# ICSL_PS_Combined_Shared.net
KiCad netlist of a schematic drawn in Altium Designer
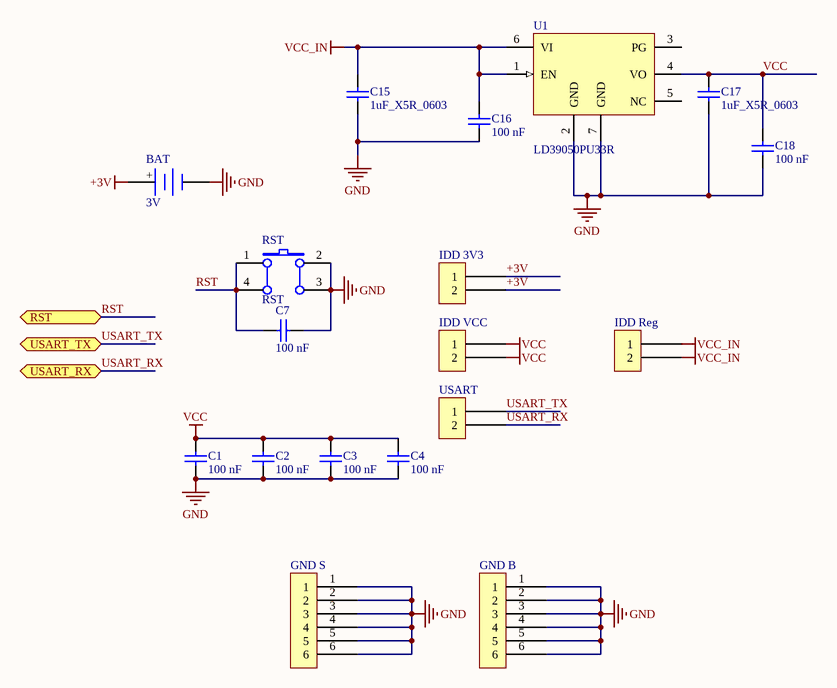
[diagram p0: ICSL_PS_Combined_Shared.SchDoc]

(export (version "E")
  (design (tool "Eeschema 10.0.6"))
  (components
    (comp (ref "BAT")
      (value "3V")
      (footprint "PCB-ltikzgtn8bqt3ncdf2ka-1")
      (description "HOLDER BATTERY DUAL CELL 20MM")
      (fields
        (field (name "MANUFACTURER") "Keystone Electronics")
        (field (name "MANUFACTURER PART NUMBER") "1026")
      )
      (libsource (lib "Octopart library") (part "SYM-19352663-1"))
    )
    (comp (ref "C1")
      (value "100 nF")
      (footprint "CAPC1608X87X35LL15T15")
      (description "Multilayer Ceramic Capacitors MLCC - SMD/SMT 50volts 82000pF X7R 10%")
      (libsource (lib "Octopart library") (part "CAP-2"))
    )
    (comp (ref "C2")
      (value "100 nF")
      (footprint "CAPC1608X87X35LL15T15")
      (description "Multilayer Ceramic Capacitors MLCC - SMD/SMT 50volts 82000pF X7R 10%")
      (libsource (lib "Octopart library") (part "CAP-2"))
    )
    (comp (ref "C3")
      (value "100 nF")
      (footprint "CAPC1608X87X35LL15T15")
      (description "Multilayer Ceramic Capacitors MLCC - SMD/SMT 50volts 82000pF X7R 10%")
      (libsource (lib "Octopart library") (part "CAP-2"))
    )
    (comp (ref "C4")
      (value "100 nF")
      (footprint "CAPC1608X87X35LL15T15")
      (description "Multilayer Ceramic Capacitors MLCC - SMD/SMT 50volts 82000pF X7R 10%")
      (libsource (lib "Octopart library") (part "CAP-2"))
    )
    (comp (ref "C7")
      (value "100 nF")
      (footprint "CAPC1608X87X35LL15T15")
      (description "Multilayer Ceramic Capacitors MLCC - SMD/SMT 50volts 82000pF X7R 10%")
      (libsource (lib "Octopart library") (part "CAP-2"))
    )
    (comp (ref "C15")
      (value "1uF_X5R_0603")
      (footprint "CAPC1608X87X35LL15T15")
      (description "Multilayer Ceramic Capacitors MLCC - SMD/SMT 50volts 82000pF X7R 10%")
      (libsource (lib "Octopart library") (part "CAP-2"))
    )
    (comp (ref "C16")
      (value "100 nF")
      (footprint "CAPC1608X87X35LL15T15")
      (description "Multilayer Ceramic Capacitors MLCC - SMD/SMT 50volts 82000pF X7R 10%")
      (libsource (lib "Octopart library") (part "CAP-2"))
    )
    (comp (ref "C17")
      (value "1uF_X5R_0603")
      (footprint "CAPC1608X87X35LL15T15")
      (description "Multilayer Ceramic Capacitors MLCC - SMD/SMT 50volts 82000pF X7R 10%")
      (libsource (lib "Octopart library") (part "CAP-2"))
    )
    (comp (ref "C18")
      (value "100 nF")
      (footprint "CAPC1608X87X35LL15T15")
      (description "Multilayer Ceramic Capacitors MLCC - SMD/SMT 50volts 82000pF X7R 10%")
      (libsource (lib "Octopart library") (part "CAP-2"))
    )
    (comp (ref "GND B")
      (value "TE Connectivity / AMP 5-146281-6")
      (footprint "PCB-ceua2d6kgzjhmbkiz2sm-1")
      (description "Header; Breakaway; 0.100 in.; PC Board; Single; 6; 0.025 in.; 0.12 in.; 3 A")
      (fields (field (name "MANUFACTURER PART NUMBER") "5-146281-2"))
      (libsource (lib "Octopart library") (part "SYM-4f28847cfb2a90ef-1"))
    )
    (comp (ref "GND S")
      (value "TE Connectivity / AMP 5-146281-6")
      (footprint "PCB-ceua2d6kgzjhmbkiz2sm-1")
      (description "Header; Breakaway; 0.100 in.; PC Board; Single; 6; 0.025 in.; 0.12 in.; 3 A")
      (fields (field (name "MANUFACTURER PART NUMBER") "5-146281-2"))
      (libsource (lib "Octopart library") (part "SYM-4f28847cfb2a90ef-1"))
    )
    (comp (ref "IDD 3V3")
      (value "TE Connectivity / AMP 3-644695-2")
      (footprint "PCB-i8m17woc8q0u0fbeoczf-1")
      (description "Connector Unshrouded Header 2 Position 2.54mm Solder Straight Thru-Hole")
      (fields (field (name "MANUFACTURER PART NUMBER") "3-644695-2"))
      (libsource (lib "Octopart library") (part "SYM-2792ecc2f21af855-1"))
    )
    (comp (ref "IDD Reg")
      (value "TE Connectivity / AMP 3-644695-2")
      (footprint "PCB-i8m17woc8q0u0fbeoczf-1")
      (description "Connector Unshrouded Header 2 Position 2.54mm Solder Straight Thru-Hole")
      (fields (field (name "MANUFACTURER PART NUMBER") "3-644695-2"))
      (libsource (lib "Octopart library") (part "SYM-2792ecc2f21af855-1"))
    )
    (comp (ref "IDD VCC")
      (value "TE Connectivity / AMP 3-644695-2")
      (footprint "PCB-i8m17woc8q0u0fbeoczf-1")
      (description "Connector Unshrouded Header 2 Position 2.54mm Solder Straight Thru-Hole")
      (fields (field (name "MANUFACTURER PART NUMBER") "3-644695-2"))
      (libsource (lib "Octopart library") (part "SYM-2792ecc2f21af855-1"))
    )
    (comp (ref "RST")
      (value "RST")
      (footprint "BP1CMS")
      (description "Switch Tactile OFF (ON) SPST Round Button Gull Wing 0.05A 24VDC 1.57N SMD T/R")
      (fields (field (name "MANUFACTURER PART NUMBER") "4-1437565-2"))
      (libsource (lib "CommunityVault") (part "SW-PUSHBUTTON"))
    )
    (comp (ref "U1")
      (value "LD39050PU33R")
      (footprint "DFN6(3X3)_A")
      (description "LD39050 Series 500 mA 3.3 V Fixed Low Noise LDO Voltage Regulator - DFN-6")
      (libsource (lib "Octopart library") (part "STM-LD39050PU-6"))
    )
    (comp (ref "USART")
      (value "TE Connectivity / AMP 3-644695-2")
      (footprint "PCB-i8m17woc8q0u0fbeoczf-1")
      (description "Connector Unshrouded Header 2 Position 2.54mm Solder Straight Thru-Hole")
      (fields (field (name "MANUFACTURER PART NUMBER") "3-644695-2"))
      (libsource (lib "Octopart library") (part "SYM-2792ecc2f21af855-1"))
    )
  )
  (nets
    (net (code "1") (name "+3V") (class "Default")
      (node (ref "BAT") (pin "1") (pinfunction "+_1") (pintype "passive"))
      (node (ref "IDD 3V3") (pin "1") (pinfunction "1_1") (pintype "passive"))
      (node (ref "IDD 3V3") (pin "2") (pinfunction "2_2") (pintype "passive"))
    )
    (net (code "2") (name "/RST") (class "Default")
      (node (ref "C7") (pin "1") (pinfunction "1_1") (pintype "passive"))
      (node (ref "RST") (pin "1") (pinfunction "A0_1") (pintype "passive"))
      (node (ref "RST") (pin "4") (pinfunction "A1_4") (pintype "passive"))
    )
    (net (code "3") (name "/USART_RX") (class "Default")
      (node (ref "USART") (pin "2") (pinfunction "2_2") (pintype "passive"))
    )
    (net (code "4") (name "/USART_TX") (class "Default")
      (node (ref "USART") (pin "1") (pinfunction "1_1") (pintype "passive"))
    )
    (net (code "5") (name "GND") (class "Default")
      (node (ref "BAT") (pin "2") (pinfunction "-_2") (pintype "passive"))
      (node (ref "C1") (pin "1") (pinfunction "1_1") (pintype "passive"))
      (node (ref "C15") (pin "1") (pinfunction "1_1") (pintype "passive"))
      (node (ref "C16") (pin "1") (pinfunction "1_1") (pintype "passive"))
      (node (ref "C17") (pin "1") (pinfunction "1_1") (pintype "passive"))
      (node (ref "C18") (pin "1") (pinfunction "1_1") (pintype "passive"))
      (node (ref "C2") (pin "1") (pinfunction "1_1") (pintype "passive"))
      (node (ref "C3") (pin "1") (pinfunction "1_1") (pintype "passive"))
      (node (ref "C4") (pin "1") (pinfunction "1_1") (pintype "passive"))
      (node (ref "C7") (pin "2") (pinfunction "2_2") (pintype "passive"))
      (node (ref "GND B") (pin "1") (pinfunction "1_1") (pintype "passive"))
      (node (ref "GND B") (pin "2") (pinfunction "2_2") (pintype "passive"))
      (node (ref "GND B") (pin "3") (pinfunction "3_3") (pintype "passive"))
      (node (ref "GND B") (pin "4") (pinfunction "4_4") (pintype "passive"))
      (node (ref "GND B") (pin "5") (pinfunction "5_5") (pintype "passive"))
      (node (ref "GND B") (pin "6") (pinfunction "6_6") (pintype "passive"))
      (node (ref "GND S") (pin "1") (pinfunction "1_1") (pintype "passive"))
      (node (ref "GND S") (pin "2") (pinfunction "2_2") (pintype "passive"))
      (node (ref "GND S") (pin "3") (pinfunction "3_3") (pintype "passive"))
      (node (ref "GND S") (pin "4") (pinfunction "4_4") (pintype "passive"))
      (node (ref "GND S") (pin "5") (pinfunction "5_5") (pintype "passive"))
      (node (ref "GND S") (pin "6") (pinfunction "6_6") (pintype "passive"))
      (node (ref "RST") (pin "2") (pinfunction "B0_2") (pintype "passive"))
      (node (ref "RST") (pin "3") (pinfunction "B1_3") (pintype "passive"))
      (node (ref "U1") (pin "2") (pinfunction "GND_2") (pintype "power_in"))
      (node (ref "U1") (pin "7") (pinfunction "GND_7") (pintype "power_in"))
    )
    (net (code "6") (name "VCC") (class "Default")
      (node (ref "C1") (pin "2") (pinfunction "2_2") (pintype "passive"))
      (node (ref "C17") (pin "2") (pinfunction "2_2") (pintype "passive"))
      (node (ref "C18") (pin "2") (pinfunction "2_2") (pintype "passive"))
      (node (ref "C2") (pin "2") (pinfunction "2_2") (pintype "passive"))
      (node (ref "C3") (pin "2") (pinfunction "2_2") (pintype "passive"))
      (node (ref "C4") (pin "2") (pinfunction "2_2") (pintype "passive"))
      (node (ref "IDD VCC") (pin "1") (pinfunction "1_1") (pintype "passive"))
      (node (ref "IDD VCC") (pin "2") (pinfunction "2_2") (pintype "passive"))
      (node (ref "U1") (pin "4") (pinfunction "VO_4") (pintype "power_in"))
    )
    (net (code "7") (name "VCC_IN") (class "Default")
      (node (ref "C15") (pin "2") (pinfunction "2_2") (pintype "passive"))
      (node (ref "C16") (pin "2") (pinfunction "2_2") (pintype "passive"))
      (node (ref "IDD Reg") (pin "1") (pinfunction "1_1") (pintype "passive"))
      (node (ref "IDD Reg") (pin "2") (pinfunction "2_2") (pintype "passive"))
      (node (ref "U1") (pin "1") (pinfunction "EN_1") (pintype "input"))
      (node (ref "U1") (pin "6") (pinfunction "VI_6") (pintype "power_in"))
    )
    (net (code "8") (name "unconnected-(U1-NC-Pad5)") (class "Default")
      (node (ref "U1") (pin "5") (pinfunction "NC_5") (pintype "passive"))
    )
    (net (code "9") (name "unconnected-(U1-PG-Pad3)") (class "Default")
      (node (ref "U1") (pin "3") (pinfunction "PG_3") (pintype "tri_state"))
    )
  )
)
